# RV1126B_EMMC.net
KiCad netlist of a schematic drawn in Altium Designer
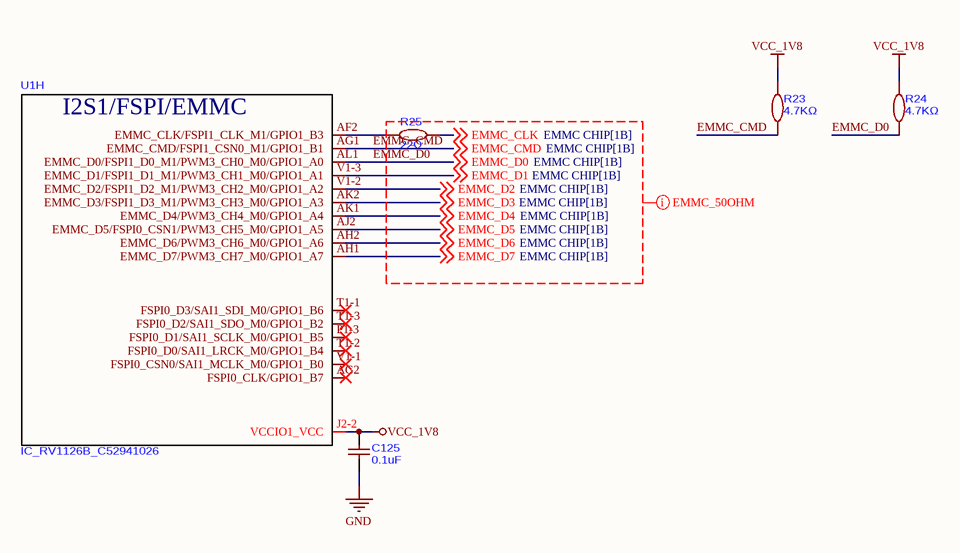
[diagram p0: RV1126B EMMC.SchDoc]

(export (version "E")
  (design (tool "Eeschema 10.0.6"))
  (components
    (comp (ref "C125")
      (value "0.1uF")
      (footprint "C0201")
      (description "0.1uF ±10% 6.3V Ceramic Capacitor X5R 0201")
      (libsource (lib "Schlib1") (part "CAP_100nF-6.3V-10%-0201_1"))
    )
    (comp (ref "R23")
      (value "4.7KΩ")
      (footprint "R0201")
      (description "RES 4.7kΩ ±1% 50mW 0201")
      (libsource (lib "Schlib1") (part "RES_4.7K-50mW-1%-0201"))
    )
    (comp (ref "R24")
      (value "4.7KΩ")
      (footprint "R0201")
      (description "RES 4.7kΩ ±1% 50mW 0201")
      (libsource (lib "Schlib1") (part "RES_4.7K-50mW-1%-0201"))
    )
    (comp (ref "R25")
      (value "22Ω")
      (footprint "R0201")
      (description "RES 22Ω ±1% 50mW 0201")
      (libsource (lib "Schlib1") (part "RES_22-50mW-1%-0201"))
    )
    (comp (ref "U1")
      (value "IC_RV1126B_C52941026")
      (footprint "CCSP-491_L14.0-W14.0-TL_RV1126B")
      (libsource (lib "Schlib1") (part "IC_RV1126B_C52941026"))
    )
  )
  (nets
    (net (code "1") (name "EMMC_CLK") (class "Default")
      (node (ref "R25") (pin "2") (pinfunction "2_2") (pintype "passive"))
    )
    (net (code "2") (name "EMMC_CMD") (class "Default")
      (node (ref "R23") (pin "1") (pinfunction "1_1") (pintype "passive"))
      (node (ref "U1") (pin "AG1") (pinfunction "EMMC_CMD/FSPI1_CSN0_M1/GPIO1_B1_AG1") (pintype "passive"))
    )
    (net (code "3") (name "EMMC_D0") (class "Default")
      (node (ref "R24") (pin "1") (pinfunction "1_1") (pintype "passive"))
      (node (ref "U1") (pin "AL1") (pinfunction "EMMC_D0/FSPI1_D0_M1/PWM3_CH0_M0/GPIO1_A0_AL1") (pintype "passive"))
    )
    (net (code "4") (name "EMMC_D1") (class "Default")
      (node (ref "U1") (pin "V1-3") (pinfunction "EMMC_D1/FSPI1_D1_M1/PWM3_CH1_M0/GPIO1_A1_V1-3") (pintype "passive"))
    )
    (net (code "5") (name "EMMC_D2") (class "Default")
      (node (ref "U1") (pin "V1-2") (pinfunction "EMMC_D2/FSPI1_D2_M1/PWM3_CH2_M0/GPIO1_A2_V1-2") (pintype "passive"))
    )
    (net (code "6") (name "EMMC_D3") (class "Default")
      (node (ref "U1") (pin "AK2") (pinfunction "EMMC_D3/FSPI1_D3_M1/PWM3_CH3_M0/GPIO1_A3_AK2") (pintype "passive"))
    )
    (net (code "7") (name "EMMC_D4") (class "Default")
      (node (ref "U1") (pin "AK1") (pinfunction "EMMC_D4/PWM3_CH4_M0/GPIO1_A4_AK1") (pintype "passive"))
    )
    (net (code "8") (name "EMMC_D5") (class "Default")
      (node (ref "U1") (pin "AJ2") (pinfunction "EMMC_D5/FSPI0_CSN1/PWM3_CH5_M0/GPIO1_A5_AJ2") (pintype "passive"))
    )
    (net (code "9") (name "EMMC_D6") (class "Default")
      (node (ref "U1") (pin "AH2") (pinfunction "EMMC_D6/PWM3_CH6_M0/GPIO1_A6_AH2") (pintype "passive"))
    )
    (net (code "10") (name "EMMC_D7") (class "Default")
      (node (ref "U1") (pin "AH1") (pinfunction "EMMC_D7/PWM3_CH7_M0/GPIO1_A7_AH1") (pintype "passive"))
    )
    (net (code "11") (name "GND") (class "Default")
      (node (ref "C125") (pin "1") (pinfunction "1_1") (pintype "passive"))
    )
    (net (code "12") (name "Net-(U1H-EMMC_CLK{slash}FSPI1_CLK_M1{slash}GPIO1_B3)") (class "Default")
      (node (ref "R25") (pin "1") (pinfunction "1_1") (pintype "passive"))
      (node (ref "U1") (pin "AF2") (pinfunction "EMMC_CLK/FSPI1_CLK_M1/GPIO1_B3_AF2") (pintype "passive"))
    )
    (net (code "13") (name "VCC_1V8") (class "Default")
      (node (ref "C125") (pin "2") (pinfunction "2_2") (pintype "passive"))
      (node (ref "R23") (pin "2") (pinfunction "2_2") (pintype "passive"))
      (node (ref "R24") (pin "2") (pinfunction "2_2") (pintype "passive"))
      (node (ref "U1") (pin "J2-2") (pinfunction "VCCIO1_VCC_J2-2") (pintype "passive"))
    )
    (net (code "14") (name "unconnected-(U1H-FSPI0_CLK{slash}GPIO1_B7-PadAG2)") (class "Default")
      (node (ref "U1") (pin "AG2") (pinfunction "FSPI0_CLK/GPIO1_B7_AG2") (pintype "passive+no_connect"))
    )
    (net (code "15") (name "unconnected-(U1H-FSPI0_CSN0{slash}SAI1_MCLK_M0{slash}GPIO1_B0-PadV1-1)") (class "Default")
      (node (ref "U1") (pin "V1-1") (pinfunction "FSPI0_CSN0/SAI1_MCLK_M0/GPIO1_B0_V1-1") (pintype "passive+no_connect"))
    )
    (net (code "16") (name "unconnected-(U1H-FSPI0_D0{slash}SAI1_LRCK_M0{slash}GPIO1_B4-PadT1-2)") (class "Default")
      (node (ref "U1") (pin "T1-2") (pinfunction "FSPI0_D0/SAI1_LRCK_M0/GPIO1_B4_T1-2") (pintype "passive+no_connect"))
    )
    (net (code "17") (name "unconnected-(U1H-FSPI0_D1{slash}SAI1_SCLK_M0{slash}GPIO1_B5-PadP1-3)") (class "Default")
      (node (ref "U1") (pin "P1-3") (pinfunction "FSPI0_D1/SAI1_SCLK_M0/GPIO1_B5_P1-3") (pintype "passive+no_connect"))
    )
    (net (code "18") (name "unconnected-(U1H-FSPI0_D2{slash}SAI1_SDO_M0{slash}GPIO1_B2-PadT1-3)") (class "Default")
      (node (ref "U1") (pin "T1-3") (pinfunction "FSPI0_D2/SAI1_SDO_M0/GPIO1_B2_T1-3") (pintype "passive+no_connect"))
    )
    (net (code "19") (name "unconnected-(U1H-FSPI0_D3{slash}SAI1_SDI_M0{slash}GPIO1_B6-PadT1-1)") (class "Default")
      (node (ref "U1") (pin "T1-1") (pinfunction "FSPI0_D3/SAI1_SDI_M0/GPIO1_B6_T1-1") (pintype "passive+no_connect"))
    )
  )
)
